# PhonoIn.net
KiCad netlist of a schematic drawn in EAGLE
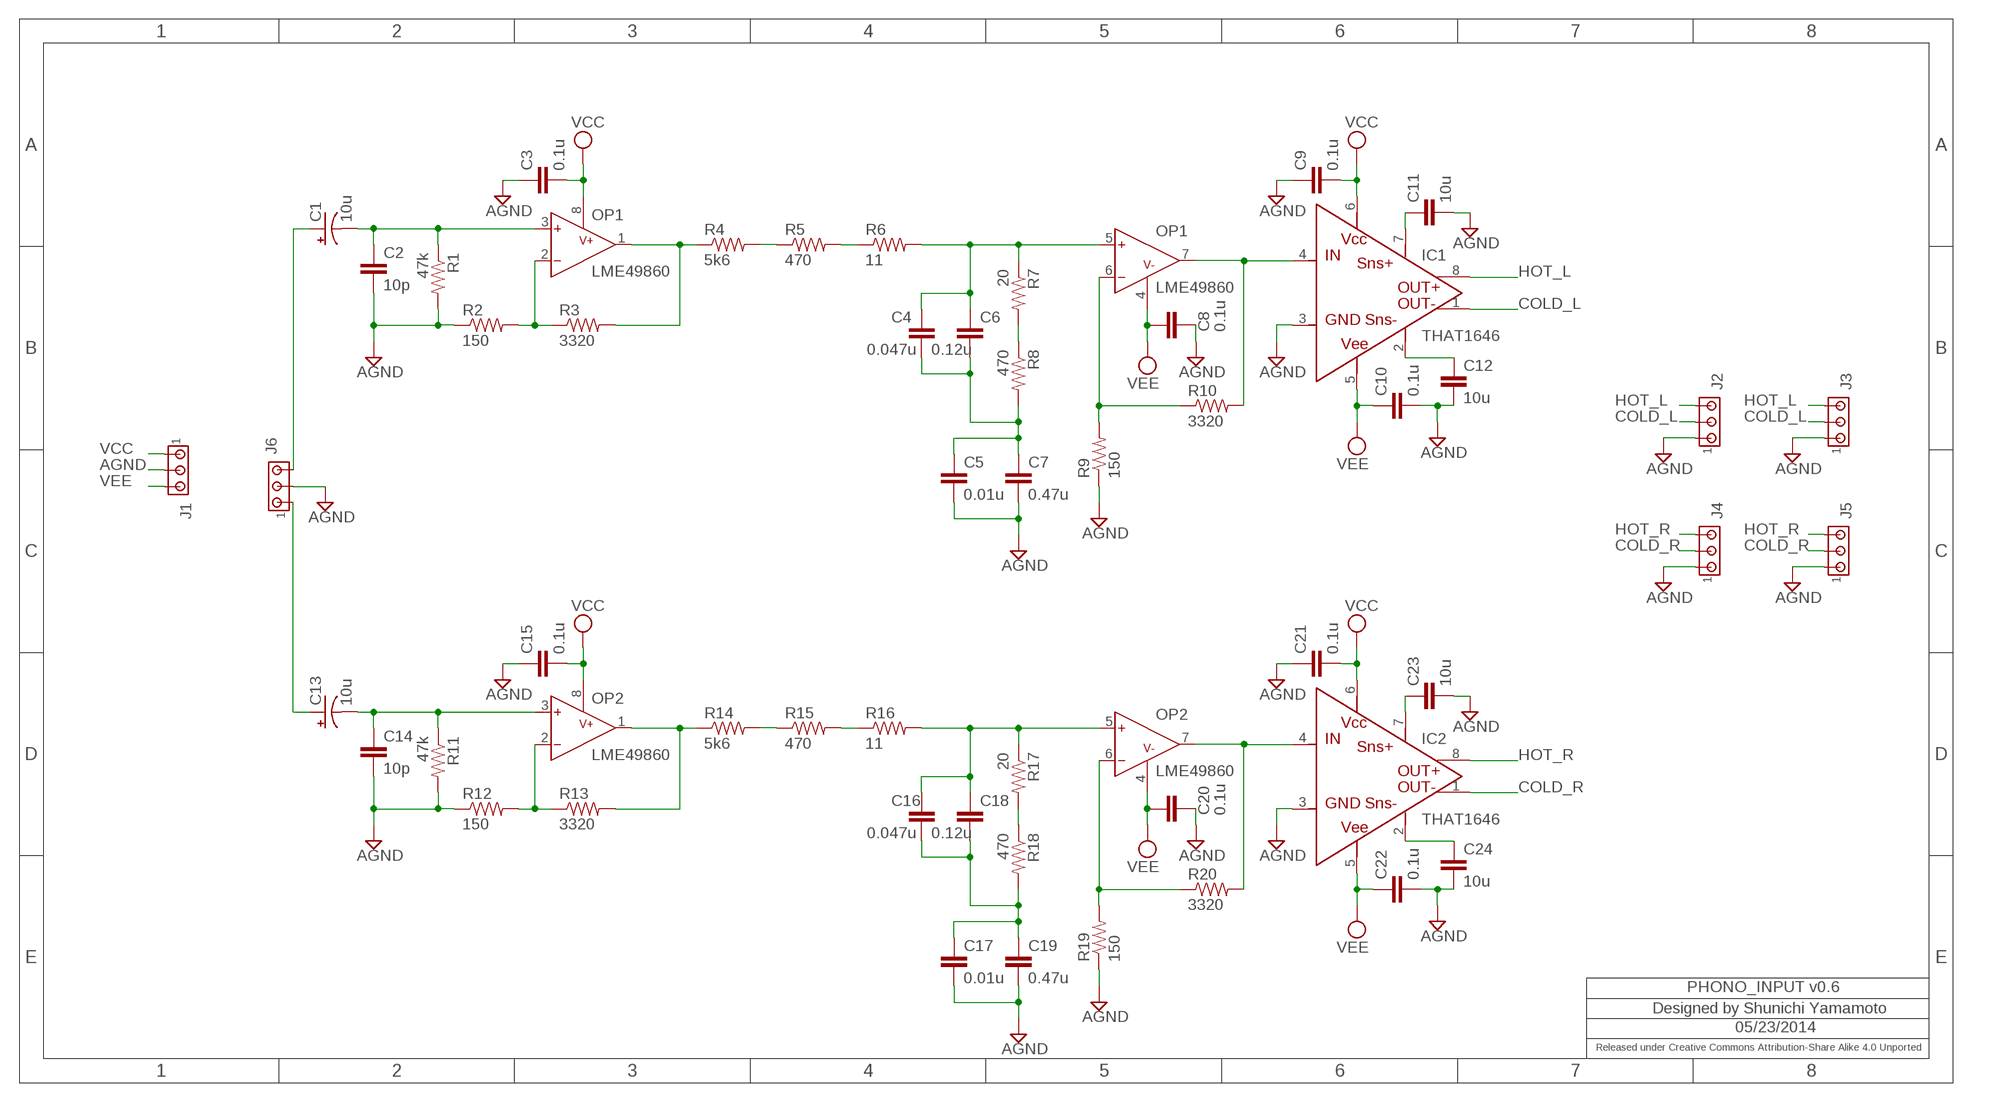
[diagram p0: schematic, sheet 1]

(export (version "E")
  (design (tool "Eeschema 10.0.6"))
  (components
    (comp (ref "C1")
      (value "10u")
      (footprint "eagle-import:UD-5X5,8_NICHICON")
      (libsource (lib "eagle-import") (part "CPOL-USUD-5X5,8"))
    )
    (comp (ref "C2")
      (value "10p")
      (footprint "eagle-import:C1608")
      (libsource (lib "eagle-import") (part "C-EUC1608"))
    )
    (comp (ref "C3")
      (value "0.1u")
      (footprint "eagle-import:C2012")
      (libsource (lib "eagle-import") (part "C-EUC2012"))
    )
    (comp (ref "C4")
      (value "0.047u")
      (footprint "eagle-import:C4833")
      (libsource (lib "eagle-import") (part "C-EUC4833"))
    )
    (comp (ref "C5")
      (value "0.01u")
      (footprint "eagle-import:C3216")
      (libsource (lib "eagle-import") (part "C-EUC3216"))
    )
    (comp (ref "C6")
      (value "0.12u")
      (footprint "eagle-import:C6041")
      (libsource (lib "eagle-import") (part "C-EUC6041"))
    )
    (comp (ref "C7")
      (value "0.47u")
      (footprint "eagle-import:C5750")
      (libsource (lib "eagle-import") (part "C-EUC5750"))
    )
    (comp (ref "C8")
      (value "0.1u")
      (footprint "eagle-import:C2012")
      (libsource (lib "eagle-import") (part "C-EUC2012"))
    )
    (comp (ref "C9")
      (value "0.1u")
      (footprint "eagle-import:C2012")
      (libsource (lib "eagle-import") (part "C-EUC2012"))
    )
    (comp (ref "C10")
      (value "0.1u")
      (footprint "eagle-import:C2012")
      (libsource (lib "eagle-import") (part "C-EUC2012"))
    )
    (comp (ref "C11")
      (value "10u")
      (footprint "eagle-import:C2012")
      (libsource (lib "eagle-import") (part "C-EUC2012"))
    )
    (comp (ref "C12")
      (value "10u")
      (footprint "eagle-import:C2012")
      (libsource (lib "eagle-import") (part "C-EUC2012"))
    )
    (comp (ref "C13")
      (value "10u")
      (footprint "eagle-import:UD-5X5,8_NICHICON")
      (libsource (lib "eagle-import") (part "CPOL-USUD-5X5,8"))
    )
    (comp (ref "C14")
      (value "10p")
      (footprint "eagle-import:C1608")
      (libsource (lib "eagle-import") (part "C-EUC1608"))
    )
    (comp (ref "C15")
      (value "0.1u")
      (footprint "eagle-import:C2012")
      (libsource (lib "eagle-import") (part "C-EUC2012"))
    )
    (comp (ref "C16")
      (value "0.047u")
      (footprint "eagle-import:C4833")
      (libsource (lib "eagle-import") (part "C-EUC4833"))
    )
    (comp (ref "C17")
      (value "0.01u")
      (footprint "eagle-import:C3216")
      (libsource (lib "eagle-import") (part "C-EUC3216"))
    )
    (comp (ref "C18")
      (value "0.12u")
      (footprint "eagle-import:C6041")
      (libsource (lib "eagle-import") (part "C-EUC6041"))
    )
    (comp (ref "C19")
      (value "0.47u")
      (footprint "eagle-import:C5750")
      (libsource (lib "eagle-import") (part "C-EUC5750"))
    )
    (comp (ref "C20")
      (value "0.1u")
      (footprint "eagle-import:C2012")
      (libsource (lib "eagle-import") (part "C-EUC2012"))
    )
    (comp (ref "C21")
      (value "0.1u")
      (footprint "eagle-import:C2012")
      (libsource (lib "eagle-import") (part "C-EUC2012"))
    )
    (comp (ref "C22")
      (value "0.1u")
      (footprint "eagle-import:C2012")
      (libsource (lib "eagle-import") (part "C-EUC2012"))
    )
    (comp (ref "C23")
      (value "10u")
      (footprint "eagle-import:C2012")
      (libsource (lib "eagle-import") (part "C-EUC2012"))
    )
    (comp (ref "C24")
      (value "10u")
      (footprint "eagle-import:C2012")
      (libsource (lib "eagle-import") (part "C-EUC2012"))
    )
    (comp (ref "IC1")
      (value "THAT1646")
      (footprint "eagle-import:SOIC8")
      (libsource (lib "eagle-import") (part "THAT1646"))
    )
    (comp (ref "IC2")
      (value "THAT1646")
      (footprint "eagle-import:SOIC8")
      (libsource (lib "eagle-import") (part "THAT1646"))
    )
    (comp (ref "J1")
      (value "MTA03-156")
      (footprint "eagle-import:1X3MTA")
      (libsource (lib "eagle-import") (part "MTA03-156"))
    )
    (comp (ref "J2")
      (value "MTA03-100")
      (footprint "eagle-import:10X03MTA")
      (libsource (lib "eagle-import") (part "MTA03-100"))
    )
    (comp (ref "J3")
      (value "MTA03-100")
      (footprint "eagle-import:10X03MTA")
      (libsource (lib "eagle-import") (part "MTA03-100"))
    )
    (comp (ref "J4")
      (value "MTA03-100")
      (footprint "eagle-import:10X03MTA")
      (libsource (lib "eagle-import") (part "MTA03-100"))
    )
    (comp (ref "J5")
      (value "MTA03-100")
      (footprint "eagle-import:10X03MTA")
      (libsource (lib "eagle-import") (part "MTA03-100"))
    )
    (comp (ref "J6")
      (value "MTA03-100")
      (footprint "eagle-import:10X03MTA")
      (libsource (lib "eagle-import") (part "MTA03-100"))
    )
    (comp (ref "OP1")
      (value "LME49860")
      (footprint "eagle-import:SOIC8")
      (libsource (lib "eagle-import") (part "LME49860"))
    )
    (comp (ref "OP2")
      (value "LME49860")
      (footprint "eagle-import:SOIC8")
      (libsource (lib "eagle-import") (part "LME49860"))
    )
    (comp (ref "R1")
      (value "47k")
      (footprint "eagle-import:0805")
      (libsource (lib "eagle-import") (part "RESISTOR0805-RES"))
    )
    (comp (ref "R2")
      (value "150")
      (footprint "eagle-import:0805")
      (libsource (lib "eagle-import") (part "RESISTOR0805-RES"))
    )
    (comp (ref "R3")
      (value "3320")
      (footprint "eagle-import:0805")
      (libsource (lib "eagle-import") (part "RESISTOR0805-RES"))
    )
    (comp (ref "R4")
      (value "5k6")
      (footprint "eagle-import:0805")
      (libsource (lib "eagle-import") (part "RESISTOR0805-RES"))
    )
    (comp (ref "R5")
      (value "470")
      (footprint "eagle-import:0805")
      (libsource (lib "eagle-import") (part "RESISTOR0805-RES"))
    )
    (comp (ref "R6")
      (value "11")
      (footprint "eagle-import:0805")
      (libsource (lib "eagle-import") (part "RESISTOR0805-RES"))
    )
    (comp (ref "R7")
      (value "20")
      (footprint "eagle-import:0805")
      (libsource (lib "eagle-import") (part "RESISTOR0805-RES"))
    )
    (comp (ref "R8")
      (value "470")
      (footprint "eagle-import:0805")
      (libsource (lib "eagle-import") (part "RESISTOR0805-RES"))
    )
    (comp (ref "R9")
      (value "150")
      (footprint "eagle-import:0805")
      (libsource (lib "eagle-import") (part "RESISTOR0805-RES"))
    )
    (comp (ref "R10")
      (value "3320")
      (footprint "eagle-import:0805")
      (libsource (lib "eagle-import") (part "RESISTOR0805-RES"))
    )
    (comp (ref "R11")
      (value "47k")
      (footprint "eagle-import:0805")
      (libsource (lib "eagle-import") (part "RESISTOR0805-RES"))
    )
    (comp (ref "R12")
      (value "150")
      (footprint "eagle-import:0805")
      (libsource (lib "eagle-import") (part "RESISTOR0805-RES"))
    )
    (comp (ref "R13")
      (value "3320")
      (footprint "eagle-import:0805")
      (libsource (lib "eagle-import") (part "RESISTOR0805-RES"))
    )
    (comp (ref "R14")
      (value "5k6")
      (footprint "eagle-import:0805")
      (libsource (lib "eagle-import") (part "RESISTOR0805-RES"))
    )
    (comp (ref "R15")
      (value "470")
      (footprint "eagle-import:0805")
      (libsource (lib "eagle-import") (part "RESISTOR0805-RES"))
    )
    (comp (ref "R16")
      (value "11")
      (footprint "eagle-import:0805")
      (libsource (lib "eagle-import") (part "RESISTOR0805-RES"))
    )
    (comp (ref "R17")
      (value "20")
      (footprint "eagle-import:0805")
      (libsource (lib "eagle-import") (part "RESISTOR0805-RES"))
    )
    (comp (ref "R18")
      (value "470")
      (footprint "eagle-import:0805")
      (libsource (lib "eagle-import") (part "RESISTOR0805-RES"))
    )
    (comp (ref "R19")
      (value "150")
      (footprint "eagle-import:0805")
      (libsource (lib "eagle-import") (part "RESISTOR0805-RES"))
    )
    (comp (ref "R20")
      (value "3320")
      (footprint "eagle-import:0805")
      (libsource (lib "eagle-import") (part "RESISTOR0805-RES"))
    )
  )
  (nets
    (net (code "1") (name "/COLD_L") (class "Default")
      (node (ref "IC1") (pin "1") (pinfunction "OUT-_1") (pintype "output"))
      (node (ref "J2") (pin "2") (pinfunction "2_2") (pintype "passive"))
      (node (ref "J3") (pin "2") (pinfunction "2_2") (pintype "passive"))
    )
    (net (code "2") (name "/COLD_R") (class "Default")
      (node (ref "IC2") (pin "1") (pinfunction "OUT-_1") (pintype "output"))
      (node (ref "J4") (pin "2") (pinfunction "2_2") (pintype "passive"))
      (node (ref "J5") (pin "2") (pinfunction "2_2") (pintype "passive"))
    )
    (net (code "3") (name "/HOT_L") (class "Default")
      (node (ref "IC1") (pin "8") (pinfunction "OUT+_8") (pintype "output"))
      (node (ref "J2") (pin "3") (pinfunction "3_3") (pintype "passive"))
      (node (ref "J3") (pin "3") (pinfunction "3_3") (pintype "passive"))
    )
    (net (code "4") (name "/HOT_R") (class "Default")
      (node (ref "IC2") (pin "8") (pinfunction "OUT+_8") (pintype "output"))
      (node (ref "J4") (pin "3") (pinfunction "3_3") (pintype "passive"))
      (node (ref "J5") (pin "3") (pinfunction "3_3") (pintype "passive"))
    )
    (net (code "5") (name "AGND") (class "Default")
      (node (ref "C10") (pin "2") (pinfunction "2_2") (pintype "passive"))
      (node (ref "C11") (pin "2") (pinfunction "2_2") (pintype "passive"))
      (node (ref "C12") (pin "2") (pinfunction "2_2") (pintype "passive"))
      (node (ref "C14") (pin "2") (pinfunction "2_2") (pintype "passive"))
      (node (ref "C15") (pin "1") (pinfunction "1_1") (pintype "passive"))
      (node (ref "C17") (pin "2") (pinfunction "2_2") (pintype "passive"))
      (node (ref "C19") (pin "P$2") (pinfunction "2_P$2") (pintype "passive"))
      (node (ref "C2") (pin "2") (pinfunction "2_2") (pintype "passive"))
      (node (ref "C20") (pin "2") (pinfunction "2_2") (pintype "passive"))
      (node (ref "C21") (pin "1") (pinfunction "1_1") (pintype "passive"))
      (node (ref "C22") (pin "2") (pinfunction "2_2") (pintype "passive"))
      (node (ref "C23") (pin "2") (pinfunction "2_2") (pintype "passive"))
      (node (ref "C24") (pin "2") (pinfunction "2_2") (pintype "passive"))
      (node (ref "C3") (pin "1") (pinfunction "1_1") (pintype "passive"))
      (node (ref "C5") (pin "2") (pinfunction "2_2") (pintype "passive"))
      (node (ref "C7") (pin "P$2") (pinfunction "2_P$2") (pintype "passive"))
      (node (ref "C8") (pin "2") (pinfunction "2_2") (pintype "passive"))
      (node (ref "C9") (pin "1") (pinfunction "1_1") (pintype "passive"))
      (node (ref "IC1") (pin "3") (pinfunction "GND_3") (pintype "input"))
      (node (ref "IC2") (pin "3") (pinfunction "GND_3") (pintype "input"))
      (node (ref "J1") (pin "2") (pinfunction "2_2") (pintype "passive"))
      (node (ref "J2") (pin "1") (pinfunction "1_1") (pintype "passive"))
      (node (ref "J3") (pin "1") (pinfunction "1_1") (pintype "passive"))
      (node (ref "J4") (pin "1") (pinfunction "1_1") (pintype "passive"))
      (node (ref "J5") (pin "1") (pinfunction "1_1") (pintype "passive"))
      (node (ref "J6") (pin "2") (pinfunction "2_2") (pintype "passive"))
      (node (ref "R1") (pin "2") (pinfunction "2_2") (pintype "passive"))
      (node (ref "R11") (pin "2") (pinfunction "2_2") (pintype "passive"))
      (node (ref "R12") (pin "1") (pinfunction "1_1") (pintype "passive"))
      (node (ref "R19") (pin "1") (pinfunction "1_1") (pintype "passive"))
      (node (ref "R2") (pin "1") (pinfunction "1_1") (pintype "passive"))
      (node (ref "R9") (pin "1") (pinfunction "1_1") (pintype "passive"))
    )
    (net (code "6") (name "Net-(C1-Pad+)") (class "Default")
      (node (ref "C1") (pin "+") (pinfunction "+_+") (pintype "passive"))
      (node (ref "J6") (pin "3") (pinfunction "3_3") (pintype "passive"))
    )
    (net (code "7") (name "Net-(C7-1)") (class "Default")
      (node (ref "C4") (pin "2") (pinfunction "2_2") (pintype "passive"))
      (node (ref "C5") (pin "1") (pinfunction "1_1") (pintype "passive"))
      (node (ref "C6") (pin "2") (pinfunction "2_2") (pintype "passive"))
      (node (ref "C7") (pin "P$1") (pinfunction "1_P$1") (pintype "passive"))
      (node (ref "R8") (pin "2") (pinfunction "2_2") (pintype "passive"))
    )
    (net (code "8") (name "Net-(C13-Pad+)") (class "Default")
      (node (ref "C13") (pin "+") (pinfunction "+_+") (pintype "passive"))
      (node (ref "J6") (pin "1") (pinfunction "1_1") (pintype "passive"))
    )
    (net (code "9") (name "Net-(C19-1)") (class "Default")
      (node (ref "C16") (pin "2") (pinfunction "2_2") (pintype "passive"))
      (node (ref "C17") (pin "1") (pinfunction "1_1") (pintype "passive"))
      (node (ref "C18") (pin "2") (pinfunction "2_2") (pintype "passive"))
      (node (ref "C19") (pin "P$1") (pinfunction "1_P$1") (pintype "passive"))
      (node (ref "R18") (pin "2") (pinfunction "2_2") (pintype "passive"))
    )
    (net (code "10") (name "Net-(IC1-IN)") (class "Default")
      (node (ref "IC1") (pin "4") (pinfunction "IN_4") (pintype "input"))
      (node (ref "OP1") (pin "7") (pinfunction "OUTB_7") (pintype "output"))
      (node (ref "R10") (pin "2") (pinfunction "2_2") (pintype "passive"))
    )
    (net (code "11") (name "Net-(IC1-SNS+)") (class "Default")
      (node (ref "C11") (pin "1") (pinfunction "1_1") (pintype "passive"))
      (node (ref "IC1") (pin "7") (pinfunction "SNS+_7") (pintype "power_in"))
    )
    (net (code "12") (name "Net-(IC1-SNS-)") (class "Default")
      (node (ref "C12") (pin "1") (pinfunction "1_1") (pintype "passive"))
      (node (ref "IC1") (pin "2") (pinfunction "SNS-_2") (pintype "input"))
    )
    (net (code "13") (name "Net-(IC2-IN)") (class "Default")
      (node (ref "IC2") (pin "4") (pinfunction "IN_4") (pintype "input"))
      (node (ref "OP2") (pin "7") (pinfunction "OUTB_7") (pintype "output"))
      (node (ref "R20") (pin "2") (pinfunction "2_2") (pintype "passive"))
    )
    (net (code "14") (name "Net-(IC2-SNS+)") (class "Default")
      (node (ref "C23") (pin "1") (pinfunction "1_1") (pintype "passive"))
      (node (ref "IC2") (pin "7") (pinfunction "SNS+_7") (pintype "power_in"))
    )
    (net (code "15") (name "Net-(IC2-SNS-)") (class "Default")
      (node (ref "C24") (pin "1") (pinfunction "1_1") (pintype "passive"))
      (node (ref "IC2") (pin "2") (pinfunction "SNS-_2") (pintype "input"))
    )
    (net (code "16") (name "Net-(OP1A-INA+)") (class "Default")
      (node (ref "C1") (pin "-") (pinfunction "-_-") (pintype "passive"))
      (node (ref "C2") (pin "1") (pinfunction "1_1") (pintype "passive"))
      (node (ref "OP1") (pin "3") (pinfunction "INA+_3") (pintype "input"))
      (node (ref "R1") (pin "1") (pinfunction "1_1") (pintype "passive"))
    )
    (net (code "17") (name "Net-(OP1A-INA-)") (class "Default")
      (node (ref "OP1") (pin "2") (pinfunction "INA-_2") (pintype "input"))
      (node (ref "R2") (pin "2") (pinfunction "2_2") (pintype "passive"))
      (node (ref "R3") (pin "1") (pinfunction "1_1") (pintype "passive"))
    )
    (net (code "18") (name "Net-(OP1A-OUTA)") (class "Default")
      (node (ref "OP1") (pin "1") (pinfunction "OUTA_1") (pintype "output"))
      (node (ref "R3") (pin "2") (pinfunction "2_2") (pintype "passive"))
      (node (ref "R4") (pin "1") (pinfunction "1_1") (pintype "passive"))
    )
    (net (code "19") (name "Net-(OP1B-INB+)") (class "Default")
      (node (ref "C4") (pin "1") (pinfunction "1_1") (pintype "passive"))
      (node (ref "C6") (pin "1") (pinfunction "1_1") (pintype "passive"))
      (node (ref "OP1") (pin "5") (pinfunction "INB+_5") (pintype "input"))
      (node (ref "R6") (pin "2") (pinfunction "2_2") (pintype "passive"))
      (node (ref "R7") (pin "1") (pinfunction "1_1") (pintype "passive"))
    )
    (net (code "20") (name "Net-(OP1B-INB-)") (class "Default")
      (node (ref "OP1") (pin "6") (pinfunction "INB-_6") (pintype "input"))
      (node (ref "R10") (pin "1") (pinfunction "1_1") (pintype "passive"))
      (node (ref "R9") (pin "2") (pinfunction "2_2") (pintype "passive"))
    )
    (net (code "21") (name "Net-(OP2A-INA+)") (class "Default")
      (node (ref "C13") (pin "-") (pinfunction "-_-") (pintype "passive"))
      (node (ref "C14") (pin "1") (pinfunction "1_1") (pintype "passive"))
      (node (ref "OP2") (pin "3") (pinfunction "INA+_3") (pintype "input"))
      (node (ref "R11") (pin "1") (pinfunction "1_1") (pintype "passive"))
    )
    (net (code "22") (name "Net-(OP2A-INA-)") (class "Default")
      (node (ref "OP2") (pin "2") (pinfunction "INA-_2") (pintype "input"))
      (node (ref "R12") (pin "2") (pinfunction "2_2") (pintype "passive"))
      (node (ref "R13") (pin "1") (pinfunction "1_1") (pintype "passive"))
    )
    (net (code "23") (name "Net-(OP2A-OUTA)") (class "Default")
      (node (ref "OP2") (pin "1") (pinfunction "OUTA_1") (pintype "output"))
      (node (ref "R13") (pin "2") (pinfunction "2_2") (pintype "passive"))
      (node (ref "R14") (pin "1") (pinfunction "1_1") (pintype "passive"))
    )
    (net (code "24") (name "Net-(OP2B-INB+)") (class "Default")
      (node (ref "C16") (pin "1") (pinfunction "1_1") (pintype "passive"))
      (node (ref "C18") (pin "1") (pinfunction "1_1") (pintype "passive"))
      (node (ref "OP2") (pin "5") (pinfunction "INB+_5") (pintype "input"))
      (node (ref "R16") (pin "2") (pinfunction "2_2") (pintype "passive"))
      (node (ref "R17") (pin "1") (pinfunction "1_1") (pintype "passive"))
    )
    (net (code "25") (name "Net-(OP2B-INB-)") (class "Default")
      (node (ref "OP2") (pin "6") (pinfunction "INB-_6") (pintype "input"))
      (node (ref "R19") (pin "2") (pinfunction "2_2") (pintype "passive"))
      (node (ref "R20") (pin "1") (pinfunction "1_1") (pintype "passive"))
    )
    (net (code "26") (name "Net-(R4-Pad2)") (class "Default")
      (node (ref "R4") (pin "2") (pinfunction "2_2") (pintype "passive"))
      (node (ref "R5") (pin "1") (pinfunction "1_1") (pintype "passive"))
    )
    (net (code "27") (name "Net-(R5-Pad2)") (class "Default")
      (node (ref "R5") (pin "2") (pinfunction "2_2") (pintype "passive"))
      (node (ref "R6") (pin "1") (pinfunction "1_1") (pintype "passive"))
    )
    (net (code "28") (name "Net-(R7-Pad2)") (class "Default")
      (node (ref "R7") (pin "2") (pinfunction "2_2") (pintype "passive"))
      (node (ref "R8") (pin "1") (pinfunction "1_1") (pintype "passive"))
    )
    (net (code "29") (name "Net-(R14-Pad2)") (class "Default")
      (node (ref "R14") (pin "2") (pinfunction "2_2") (pintype "passive"))
      (node (ref "R15") (pin "1") (pinfunction "1_1") (pintype "passive"))
    )
    (net (code "30") (name "Net-(R15-Pad2)") (class "Default")
      (node (ref "R15") (pin "2") (pinfunction "2_2") (pintype "passive"))
      (node (ref "R16") (pin "1") (pinfunction "1_1") (pintype "passive"))
    )
    (net (code "31") (name "Net-(R17-Pad2)") (class "Default")
      (node (ref "R17") (pin "2") (pinfunction "2_2") (pintype "passive"))
      (node (ref "R18") (pin "1") (pinfunction "1_1") (pintype "passive"))
    )
    (net (code "32") (name "VCC") (class "Default")
      (node (ref "C15") (pin "2") (pinfunction "2_2") (pintype "passive"))
      (node (ref "C21") (pin "2") (pinfunction "2_2") (pintype "passive"))
      (node (ref "C3") (pin "2") (pinfunction "2_2") (pintype "passive"))
      (node (ref "C9") (pin "2") (pinfunction "2_2") (pintype "passive"))
      (node (ref "IC1") (pin "6") (pinfunction "VCC_6") (pintype "bidirectional"))
      (node (ref "IC2") (pin "6") (pinfunction "VCC_6") (pintype "bidirectional"))
      (node (ref "J1") (pin "1") (pinfunction "1_1") (pintype "passive"))
      (node (ref "OP1") (pin "8") (pinfunction "V+_8") (pintype "power_in"))
      (node (ref "OP2") (pin "8") (pinfunction "V+_8") (pintype "power_in"))
    )
    (net (code "33") (name "VEE") (class "Default")
      (node (ref "C10") (pin "1") (pinfunction "1_1") (pintype "passive"))
      (node (ref "C20") (pin "1") (pinfunction "1_1") (pintype "passive"))
      (node (ref "C22") (pin "1") (pinfunction "1_1") (pintype "passive"))
      (node (ref "C8") (pin "1") (pinfunction "1_1") (pintype "passive"))
      (node (ref "IC1") (pin "5") (pinfunction "VEE_5") (pintype "input"))
      (node (ref "IC2") (pin "5") (pinfunction "VEE_5") (pintype "input"))
      (node (ref "J1") (pin "3") (pinfunction "3_3") (pintype "passive"))
      (node (ref "OP1") (pin "4") (pinfunction "V-_4") (pintype "power_in"))
      (node (ref "OP2") (pin "4") (pinfunction "V-_4") (pintype "power_in"))
    )
  )
)
